# ProPrj_keyboard_2024-11-03.net
KiCad netlist of a schematic drawn in EasyEDA Pro
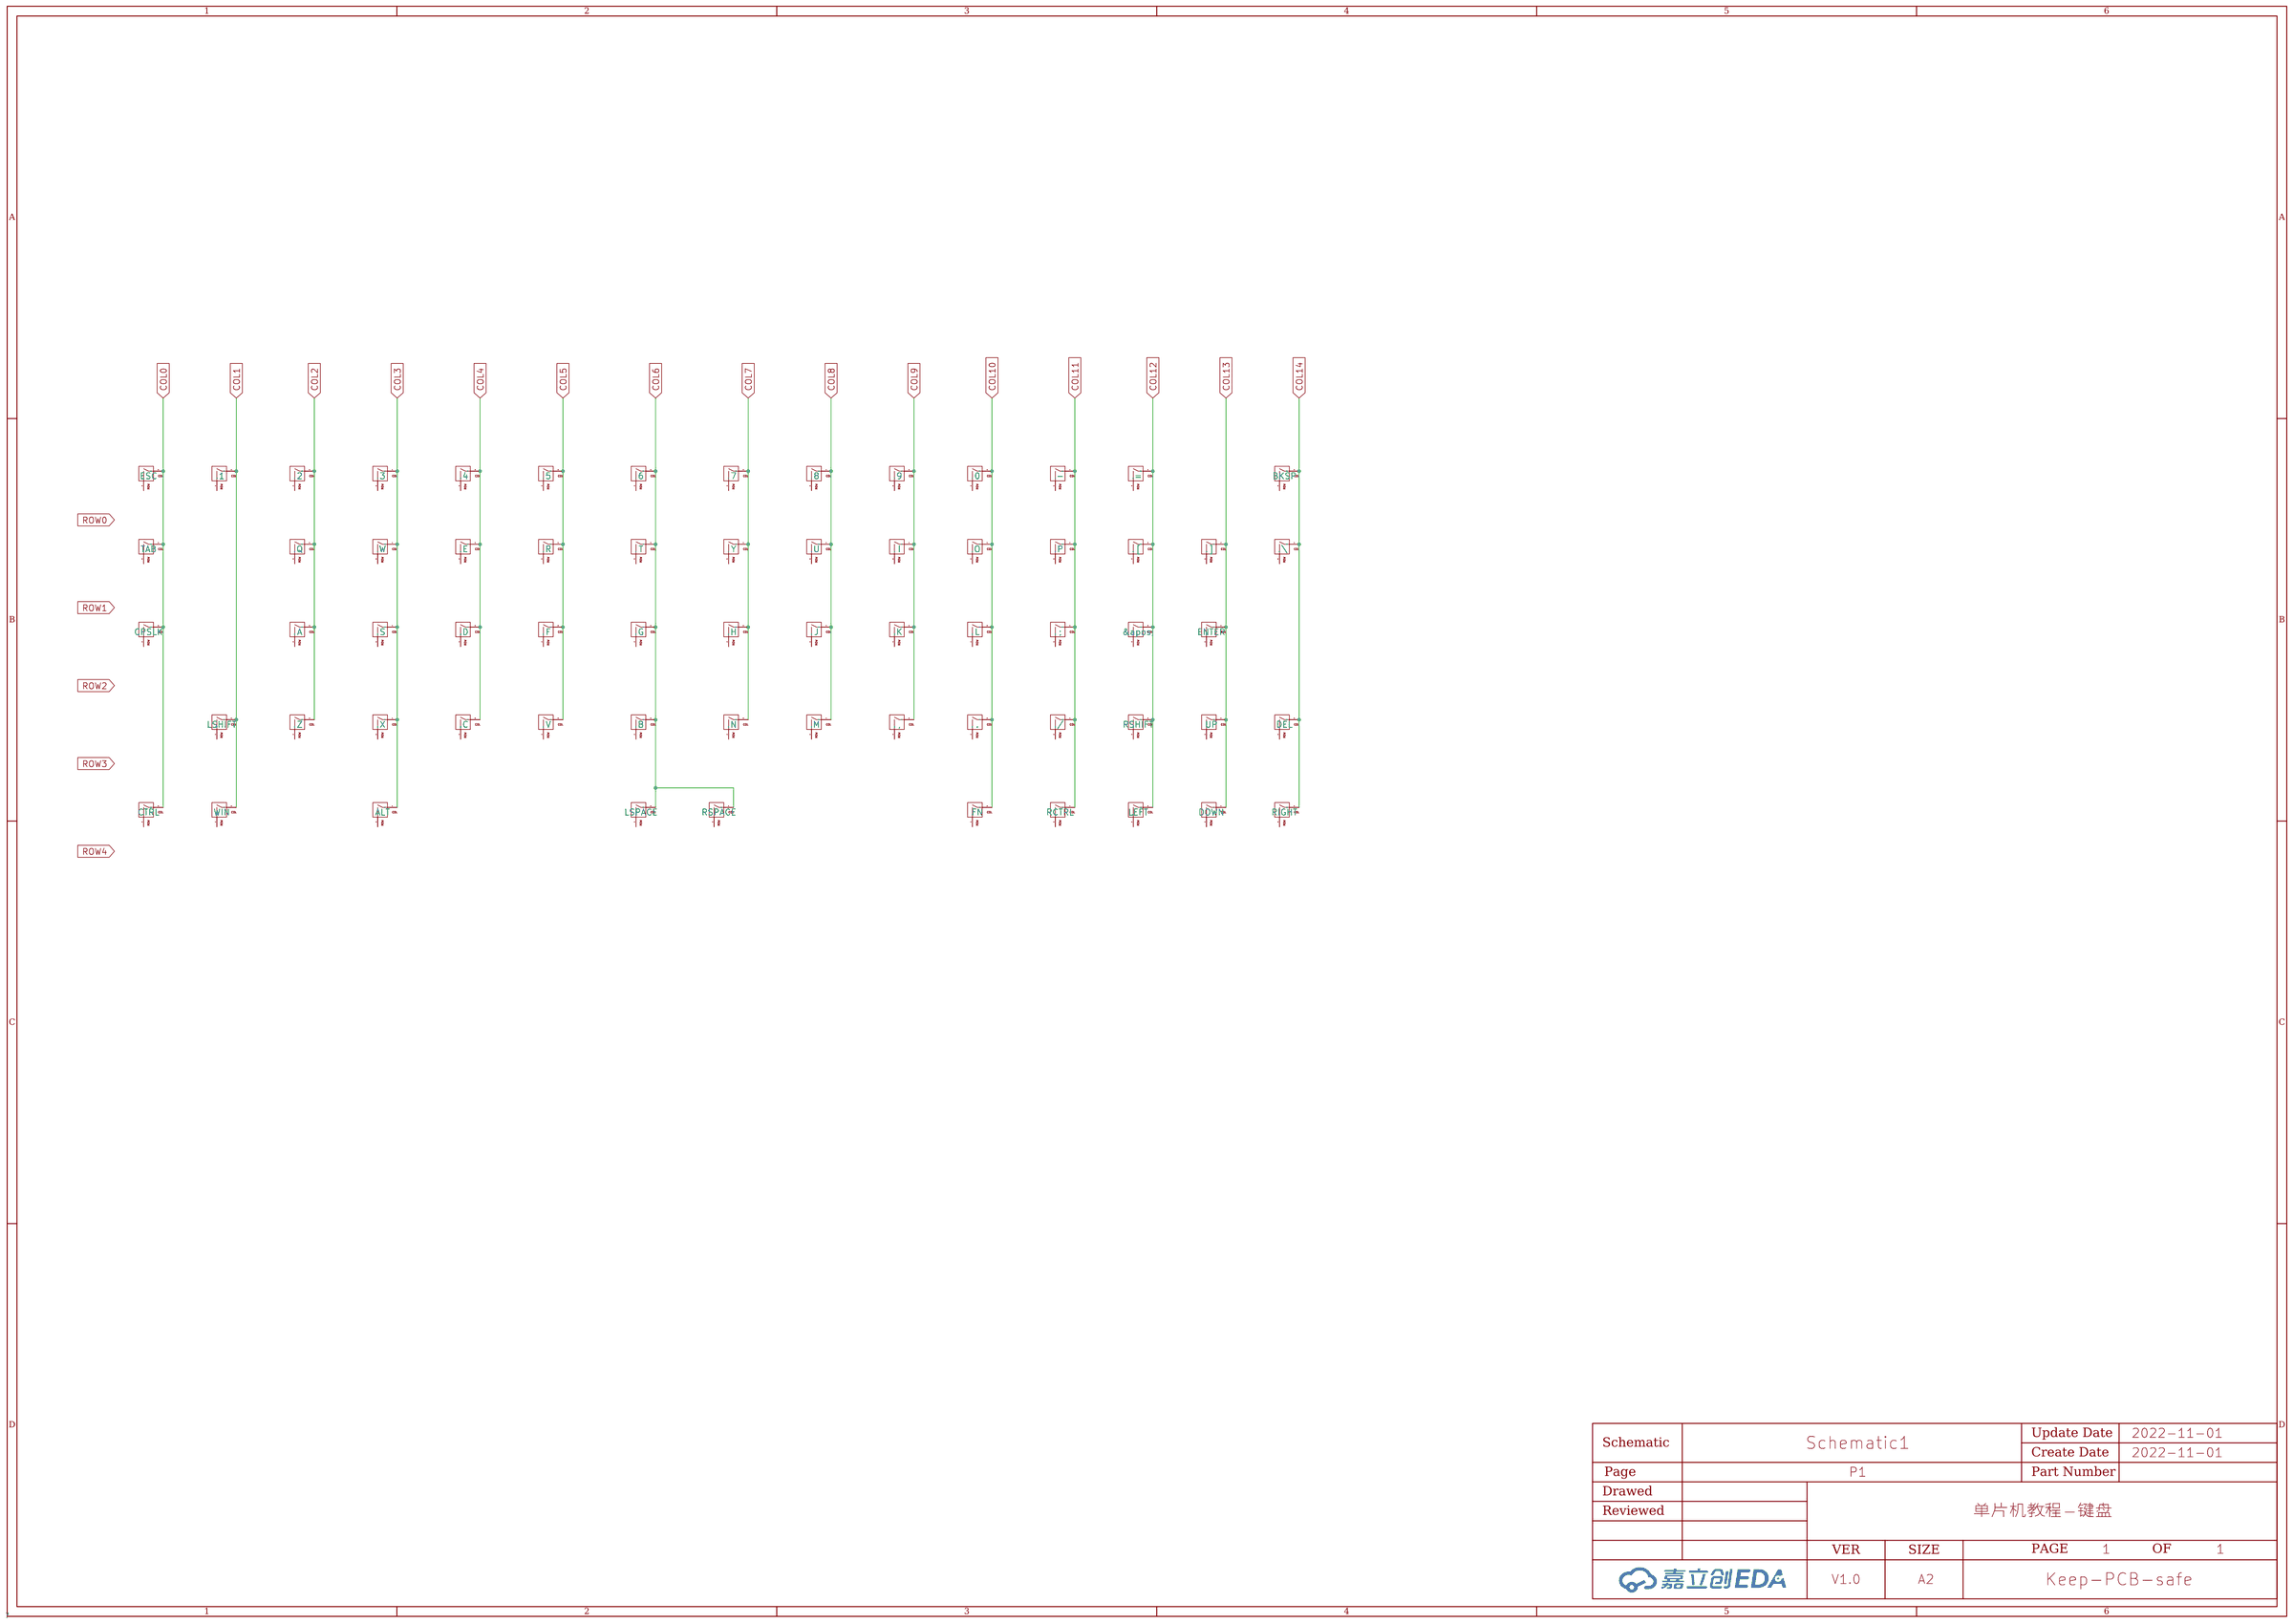
[diagram p0: schematic sheet]

(export (version "E")
  (design (tool "Eeschema 10.0.6"))
  (components
    (comp (ref "&apos;")
      (value "MX-NoLED")
      (footprint "easyedapro:MX_ALPS_HYBRID:MXONLY-1U")
      (libsource (lib "easyedapro") (part "MX-NoLED"))
    )
    (comp (ref ",")
      (value "MX-NoLED")
      (footprint "easyedapro:MX_ALPS_HYBRID:MXONLY-1U")
      (libsource (lib "easyedapro") (part "MX-NoLED"))
    )
    (comp (ref "-")
      (value "MX-NoLED")
      (footprint "easyedapro:MX_ALPS_HYBRID:MXONLY-1U")
      (libsource (lib "easyedapro") (part "MX-NoLED"))
    )
    (comp (ref ".")
      (value "MX-NoLED")
      (footprint "easyedapro:MX_ALPS_HYBRID:MXONLY-1U")
      (libsource (lib "easyedapro") (part "MX-NoLED"))
    )
    (comp (ref "/")
      (value "MX-NoLED")
      (footprint "easyedapro:MX_ALPS_HYBRID:MXONLY-1U")
      (libsource (lib "easyedapro") (part "MX-NoLED"))
    )
    (comp (ref "0")
      (value "MX-NoLED")
      (footprint "easyedapro:MX_ALPS_HYBRID:MXONLY-1U")
      (libsource (lib "easyedapro") (part "MX-NoLED"))
    )
    (comp (ref "1")
      (value "MX-NoLED")
      (footprint "easyedapro:MX_ALPS_HYBRID:MXONLY-1U")
      (libsource (lib "easyedapro") (part "MX-NoLED"))
    )
    (comp (ref "2")
      (value "MX-NoLED")
      (footprint "easyedapro:MX_ALPS_HYBRID:MXONLY-1U")
      (libsource (lib "easyedapro") (part "MX-NoLED"))
    )
    (comp (ref "3")
      (value "MX-NoLED")
      (footprint "easyedapro:MX_ALPS_HYBRID:MXONLY-1U")
      (libsource (lib "easyedapro") (part "MX-NoLED"))
    )
    (comp (ref "4")
      (value "MX-NoLED")
      (footprint "easyedapro:MX_ALPS_HYBRID:MXONLY-1U")
      (libsource (lib "easyedapro") (part "MX-NoLED"))
    )
    (comp (ref "5")
      (value "MX-NoLED")
      (footprint "easyedapro:MX_ALPS_HYBRID:MXONLY-1U")
      (libsource (lib "easyedapro") (part "MX-NoLED"))
    )
    (comp (ref "6")
      (value "MX-NoLED")
      (footprint "easyedapro:MX_ALPS_HYBRID:MXONLY-1U")
      (libsource (lib "easyedapro") (part "MX-NoLED"))
    )
    (comp (ref "7")
      (value "MX-NoLED")
      (footprint "easyedapro:MX_ALPS_HYBRID:MXONLY-1U")
      (libsource (lib "easyedapro") (part "MX-NoLED"))
    )
    (comp (ref "8")
      (value "MX-NoLED")
      (footprint "easyedapro:MX_ALPS_HYBRID:MXONLY-1U")
      (libsource (lib "easyedapro") (part "MX-NoLED"))
    )
    (comp (ref "9")
      (value "MX-NoLED")
      (footprint "easyedapro:MX_ALPS_HYBRID:MXONLY-1U")
      (libsource (lib "easyedapro") (part "MX-NoLED"))
    )
    (comp (ref ";")
      (value "MX-NoLED")
      (footprint "easyedapro:MX_ALPS_HYBRID:MXONLY-1U")
      (libsource (lib "easyedapro") (part "MX-NoLED"))
    )
    (comp (ref "=")
      (value "MX-NoLED")
      (footprint "easyedapro:MX_ALPS_HYBRID:MXONLY-1U")
      (libsource (lib "easyedapro") (part "MX-NoLED"))
    )
    (comp (ref "A")
      (value "MX-NoLED")
      (footprint "easyedapro:MX_ALPS_HYBRID:MXONLY-1U")
      (libsource (lib "easyedapro") (part "MX-NoLED"))
    )
    (comp (ref "ALT")
      (value "MX-NoLED")
      (footprint "easyedapro:MX_ALPS_HYBRID:MXONLY-1U")
      (libsource (lib "easyedapro") (part "MX-NoLED"))
    )
    (comp (ref "B")
      (value "MX-NoLED")
      (footprint "easyedapro:MX_ALPS_HYBRID:MXONLY-1U")
      (libsource (lib "easyedapro") (part "MX-NoLED"))
    )
    (comp (ref "BKSP")
      (value "MX-NoLED")
      (footprint "easyedapro:MX_ALPS_HYBRID:MXONLY-1U")
      (libsource (lib "easyedapro") (part "MX-NoLED"))
    )
    (comp (ref "C")
      (value "MX-NoLED")
      (footprint "easyedapro:MX_ALPS_HYBRID:MXONLY-1U")
      (libsource (lib "easyedapro") (part "MX-NoLED"))
    )
    (comp (ref "CPSLK")
      (value "MX-NoLED")
      (footprint "easyedapro:MX_ALPS_HYBRID:MXONLY-1U")
      (libsource (lib "easyedapro") (part "MX-NoLED"))
    )
    (comp (ref "CTRL")
      (value "MX-NoLED")
      (footprint "easyedapro:MX_ALPS_HYBRID:MXONLY-1U")
      (libsource (lib "easyedapro") (part "MX-NoLED"))
    )
    (comp (ref "D")
      (value "MX-NoLED")
      (footprint "easyedapro:MX_ALPS_HYBRID:MXONLY-1U")
      (libsource (lib "easyedapro") (part "MX-NoLED"))
    )
    (comp (ref "DEL")
      (value "MX-NoLED")
      (footprint "easyedapro:MX_ALPS_HYBRID:MXONLY-1U")
      (libsource (lib "easyedapro") (part "MX-NoLED"))
    )
    (comp (ref "DOWN")
      (value "MX-NoLED")
      (footprint "easyedapro:MX_ALPS_HYBRID:MXONLY-1U")
      (libsource (lib "easyedapro") (part "MX-NoLED"))
    )
    (comp (ref "E")
      (value "MX-NoLED")
      (footprint "easyedapro:MX_ALPS_HYBRID:MXONLY-1U")
      (libsource (lib "easyedapro") (part "MX-NoLED"))
    )
    (comp (ref "ENTER")
      (value "MX-NoLED")
      (footprint "easyedapro:MX_ALPS_HYBRID:MXONLY-1U")
      (libsource (lib "easyedapro") (part "MX-NoLED"))
    )
    (comp (ref "ESC")
      (value "MX-NoLED")
      (footprint "easyedapro:MX_ALPS_HYBRID:MXONLY-1U")
      (libsource (lib "easyedapro") (part "MX-NoLED"))
    )
    (comp (ref "F")
      (value "MX-NoLED")
      (footprint "easyedapro:MX_ALPS_HYBRID:MXONLY-1U")
      (libsource (lib "easyedapro") (part "MX-NoLED"))
    )
    (comp (ref "FN")
      (value "MX-NoLED")
      (footprint "easyedapro:MX_ALPS_HYBRID:MXONLY-1U")
      (libsource (lib "easyedapro") (part "MX-NoLED"))
    )
    (comp (ref "G")
      (value "MX-NoLED")
      (footprint "easyedapro:MX_ALPS_HYBRID:MXONLY-1U")
      (libsource (lib "easyedapro") (part "MX-NoLED"))
    )
    (comp (ref "H")
      (value "MX-NoLED")
      (footprint "easyedapro:MX_ALPS_HYBRID:MXONLY-1U")
      (libsource (lib "easyedapro") (part "MX-NoLED"))
    )
    (comp (ref "I")
      (value "MX-NoLED")
      (footprint "easyedapro:MX_ALPS_HYBRID:MXONLY-1U")
      (libsource (lib "easyedapro") (part "MX-NoLED"))
    )
    (comp (ref "J")
      (value "MX-NoLED")
      (footprint "easyedapro:MX_ALPS_HYBRID:MXONLY-1U")
      (libsource (lib "easyedapro") (part "MX-NoLED"))
    )
    (comp (ref "K")
      (value "MX-NoLED")
      (footprint "easyedapro:MX_ALPS_HYBRID:MXONLY-1U")
      (libsource (lib "easyedapro") (part "MX-NoLED"))
    )
    (comp (ref "L")
      (value "MX-NoLED")
      (footprint "easyedapro:MX_ALPS_HYBRID:MXONLY-1U")
      (libsource (lib "easyedapro") (part "MX-NoLED"))
    )
    (comp (ref "LEFT")
      (value "MX-NoLED")
      (footprint "easyedapro:MX_ALPS_HYBRID:MXONLY-1U")
      (libsource (lib "easyedapro") (part "MX-NoLED"))
    )
    (comp (ref "LSHIFT")
      (value "MX-NoLED")
      (footprint "easyedapro:MX_ALPS_HYBRID:MXONLY-1U")
      (libsource (lib "easyedapro") (part "MX-NoLED"))
    )
    (comp (ref "LSPACE")
      (value "MX-NoLED")
      (footprint "easyedapro:MX_ALPS_HYBRID:MXONLY-1U")
      (libsource (lib "easyedapro") (part "MX-NoLED"))
    )
    (comp (ref "M")
      (value "MX-NoLED")
      (footprint "easyedapro:MX_ALPS_HYBRID:MXONLY-1U")
      (libsource (lib "easyedapro") (part "MX-NoLED"))
    )
    (comp (ref "N")
      (value "MX-NoLED")
      (footprint "easyedapro:MX_ALPS_HYBRID:MXONLY-1U")
      (libsource (lib "easyedapro") (part "MX-NoLED"))
    )
    (comp (ref "O")
      (value "MX-NoLED")
      (footprint "easyedapro:MX_ALPS_HYBRID:MXONLY-1U")
      (libsource (lib "easyedapro") (part "MX-NoLED"))
    )
    (comp (ref "P")
      (value "MX-NoLED")
      (footprint "easyedapro:MX_ALPS_HYBRID:MXONLY-1U")
      (libsource (lib "easyedapro") (part "MX-NoLED"))
    )
    (comp (ref "Q")
      (value "MX-NoLED")
      (footprint "easyedapro:MX_ALPS_HYBRID:MXONLY-1U")
      (libsource (lib "easyedapro") (part "MX-NoLED"))
    )
    (comp (ref "R")
      (value "MX-NoLED")
      (footprint "easyedapro:MX_ALPS_HYBRID:MXONLY-1U")
      (libsource (lib "easyedapro") (part "MX-NoLED"))
    )
    (comp (ref "RCTRL")
      (value "MX-NoLED")
      (footprint "easyedapro:MX_ALPS_HYBRID:MXONLY-1U")
      (libsource (lib "easyedapro") (part "MX-NoLED"))
    )
    (comp (ref "RIGHT")
      (value "MX-NoLED")
      (footprint "easyedapro:MX_ALPS_HYBRID:MXONLY-1U")
      (libsource (lib "easyedapro") (part "MX-NoLED"))
    )
    (comp (ref "RSHIFT")
      (value "MX-NoLED")
      (footprint "easyedapro:MX_ALPS_HYBRID:MXONLY-1U")
      (libsource (lib "easyedapro") (part "MX-NoLED"))
    )
    (comp (ref "RSPACE")
      (value "MX-NoLED")
      (footprint "easyedapro:MX_ALPS_HYBRID:MXONLY-1U")
      (libsource (lib "easyedapro") (part "MX-NoLED"))
    )
    (comp (ref "S")
      (value "MX-NoLED")
      (footprint "easyedapro:MX_ALPS_HYBRID:MXONLY-1U")
      (libsource (lib "easyedapro") (part "MX-NoLED"))
    )
    (comp (ref "T")
      (value "MX-NoLED")
      (footprint "easyedapro:MX_ALPS_HYBRID:MXONLY-1U")
      (libsource (lib "easyedapro") (part "MX-NoLED"))
    )
    (comp (ref "TAB")
      (value "MX-NoLED")
      (footprint "easyedapro:MX_ALPS_HYBRID:MXONLY-1U")
      (libsource (lib "easyedapro") (part "MX-NoLED"))
    )
    (comp (ref "U")
      (value "MX-NoLED")
      (footprint "easyedapro:MX_ALPS_HYBRID:MXONLY-1U")
      (libsource (lib "easyedapro") (part "MX-NoLED"))
    )
    (comp (ref "UP")
      (value "MX-NoLED")
      (footprint "easyedapro:MX_ALPS_HYBRID:MXONLY-1U")
      (libsource (lib "easyedapro") (part "MX-NoLED"))
    )
    (comp (ref "V")
      (value "MX-NoLED")
      (footprint "easyedapro:MX_ALPS_HYBRID:MXONLY-1U")
      (libsource (lib "easyedapro") (part "MX-NoLED"))
    )
    (comp (ref "W")
      (value "MX-NoLED")
      (footprint "easyedapro:MX_ALPS_HYBRID:MXONLY-1U")
      (libsource (lib "easyedapro") (part "MX-NoLED"))
    )
    (comp (ref "WIN")
      (value "MX-NoLED")
      (footprint "easyedapro:MX_ALPS_HYBRID:MXONLY-1U")
      (libsource (lib "easyedapro") (part "MX-NoLED"))
    )
    (comp (ref "X")
      (value "MX-NoLED")
      (footprint "easyedapro:MX_ALPS_HYBRID:MXONLY-1U")
      (libsource (lib "easyedapro") (part "MX-NoLED"))
    )
    (comp (ref "Y")
      (value "MX-NoLED")
      (footprint "easyedapro:MX_ALPS_HYBRID:MXONLY-1U")
      (libsource (lib "easyedapro") (part "MX-NoLED"))
    )
    (comp (ref "Z")
      (value "MX-NoLED")
      (footprint "easyedapro:MX_ALPS_HYBRID:MXONLY-1U")
      (libsource (lib "easyedapro") (part "MX-NoLED"))
    )
    (comp (ref "[")
      (value "MX-NoLED")
      (footprint "easyedapro:MX_ALPS_HYBRID:MXONLY-1U")
      (libsource (lib "easyedapro") (part "MX-NoLED"))
    )
    (comp (ref "\\")
      (value "MX-NoLED")
      (footprint "easyedapro:MX_ALPS_HYBRID:MXONLY-1U")
      (libsource (lib "easyedapro") (part "MX-NoLED"))
    )
    (comp (ref "]")
      (value "MX-NoLED")
      (footprint "easyedapro:MX_ALPS_HYBRID:MXONLY-1U")
      (libsource (lib "easyedapro") (part "MX-NoLED"))
    )
  )
  (nets
    (net (code "1") (name "COL0") (class "Default")
      (node (ref "CPSLK") (pin "1") (pinfunction "COL_1") (pintype "unspecified"))
      (node (ref "CTRL") (pin "1") (pinfunction "COL_1") (pintype "unspecified"))
      (node (ref "ESC") (pin "1") (pinfunction "COL_1") (pintype "unspecified"))
      (node (ref "TAB") (pin "1") (pinfunction "COL_1") (pintype "unspecified"))
    )
    (net (code "2") (name "COL1") (class "Default")
      (node (ref "1") (pin "1") (pinfunction "COL_1") (pintype "unspecified"))
      (node (ref "LSHIFT") (pin "1") (pinfunction "COL_1") (pintype "unspecified"))
      (node (ref "WIN") (pin "1") (pinfunction "COL_1") (pintype "unspecified"))
    )
    (net (code "3") (name "COL2") (class "Default")
      (node (ref "2") (pin "1") (pinfunction "COL_1") (pintype "unspecified"))
      (node (ref "A") (pin "1") (pinfunction "COL_1") (pintype "unspecified"))
      (node (ref "Q") (pin "1") (pinfunction "COL_1") (pintype "unspecified"))
      (node (ref "Z") (pin "1") (pinfunction "COL_1") (pintype "unspecified"))
    )
    (net (code "4") (name "COL3") (class "Default")
      (node (ref "3") (pin "1") (pinfunction "COL_1") (pintype "unspecified"))
      (node (ref "ALT") (pin "1") (pinfunction "COL_1") (pintype "unspecified"))
      (node (ref "S") (pin "1") (pinfunction "COL_1") (pintype "unspecified"))
      (node (ref "W") (pin "1") (pinfunction "COL_1") (pintype "unspecified"))
      (node (ref "X") (pin "1") (pinfunction "COL_1") (pintype "unspecified"))
    )
    (net (code "5") (name "COL4") (class "Default")
      (node (ref "4") (pin "1") (pinfunction "COL_1") (pintype "unspecified"))
      (node (ref "C") (pin "1") (pinfunction "COL_1") (pintype "unspecified"))
      (node (ref "D") (pin "1") (pinfunction "COL_1") (pintype "unspecified"))
      (node (ref "E") (pin "1") (pinfunction "COL_1") (pintype "unspecified"))
    )
    (net (code "6") (name "COL5") (class "Default")
      (node (ref "5") (pin "1") (pinfunction "COL_1") (pintype "unspecified"))
      (node (ref "F") (pin "1") (pinfunction "COL_1") (pintype "unspecified"))
      (node (ref "R") (pin "1") (pinfunction "COL_1") (pintype "unspecified"))
      (node (ref "V") (pin "1") (pinfunction "COL_1") (pintype "unspecified"))
    )
    (net (code "7") (name "COL6") (class "Default")
      (node (ref "6") (pin "1") (pinfunction "COL_1") (pintype "unspecified"))
      (node (ref "B") (pin "1") (pinfunction "COL_1") (pintype "unspecified"))
      (node (ref "G") (pin "1") (pinfunction "COL_1") (pintype "unspecified"))
      (node (ref "LSPACE") (pin "1") (pinfunction "COL_1") (pintype "unspecified"))
      (node (ref "RSPACE") (pin "1") (pinfunction "COL_1") (pintype "unspecified"))
      (node (ref "T") (pin "1") (pinfunction "COL_1") (pintype "unspecified"))
    )
    (net (code "8") (name "COL7") (class "Default")
      (node (ref "7") (pin "1") (pinfunction "COL_1") (pintype "unspecified"))
      (node (ref "H") (pin "1") (pinfunction "COL_1") (pintype "unspecified"))
      (node (ref "N") (pin "1") (pinfunction "COL_1") (pintype "unspecified"))
      (node (ref "Y") (pin "1") (pinfunction "COL_1") (pintype "unspecified"))
    )
    (net (code "9") (name "COL8") (class "Default")
      (node (ref "8") (pin "1") (pinfunction "COL_1") (pintype "unspecified"))
      (node (ref "J") (pin "1") (pinfunction "COL_1") (pintype "unspecified"))
      (node (ref "M") (pin "1") (pinfunction "COL_1") (pintype "unspecified"))
      (node (ref "U") (pin "1") (pinfunction "COL_1") (pintype "unspecified"))
    )
    (net (code "10") (name "COL9") (class "Default")
      (node (ref ",") (pin "1") (pinfunction "COL_1") (pintype "unspecified"))
      (node (ref "9") (pin "1") (pinfunction "COL_1") (pintype "unspecified"))
      (node (ref "I") (pin "1") (pinfunction "COL_1") (pintype "unspecified"))
      (node (ref "K") (pin "1") (pinfunction "COL_1") (pintype "unspecified"))
    )
    (net (code "11") (name "COL10") (class "Default")
      (node (ref ".") (pin "1") (pinfunction "COL_1") (pintype "unspecified"))
      (node (ref "0") (pin "1") (pinfunction "COL_1") (pintype "unspecified"))
      (node (ref "FN") (pin "1") (pinfunction "COL_1") (pintype "unspecified"))
      (node (ref "L") (pin "1") (pinfunction "COL_1") (pintype "unspecified"))
      (node (ref "O") (pin "1") (pinfunction "COL_1") (pintype "unspecified"))
    )
    (net (code "12") (name "COL11") (class "Default")
      (node (ref "-") (pin "1") (pinfunction "COL_1") (pintype "unspecified"))
      (node (ref "/") (pin "1") (pinfunction "COL_1") (pintype "unspecified"))
      (node (ref ";") (pin "1") (pinfunction "COL_1") (pintype "unspecified"))
      (node (ref "P") (pin "1") (pinfunction "COL_1") (pintype "unspecified"))
      (node (ref "RCTRL") (pin "1") (pinfunction "COL_1") (pintype "unspecified"))
    )
    (net (code "13") (name "COL12") (class "Default")
      (node (ref "&apos;") (pin "1") (pinfunction "COL_1") (pintype "unspecified"))
      (node (ref "=") (pin "1") (pinfunction "COL_1") (pintype "unspecified"))
      (node (ref "LEFT") (pin "1") (pinfunction "COL_1") (pintype "unspecified"))
      (node (ref "RSHIFT") (pin "1") (pinfunction "COL_1") (pintype "unspecified"))
      (node (ref "[") (pin "1") (pinfunction "COL_1") (pintype "unspecified"))
    )
    (net (code "14") (name "COL13") (class "Default")
      (node (ref "DOWN") (pin "1") (pinfunction "COL_1") (pintype "unspecified"))
      (node (ref "ENTER") (pin "1") (pinfunction "COL_1") (pintype "unspecified"))
      (node (ref "UP") (pin "1") (pinfunction "COL_1") (pintype "unspecified"))
      (node (ref "]") (pin "1") (pinfunction "COL_1") (pintype "unspecified"))
    )
    (net (code "15") (name "COL14") (class "Default")
      (node (ref "BKSP") (pin "1") (pinfunction "COL_1") (pintype "unspecified"))
      (node (ref "DEL") (pin "1") (pinfunction "COL_1") (pintype "unspecified"))
      (node (ref "RIGHT") (pin "1") (pinfunction "COL_1") (pintype "unspecified"))
      (node (ref "\\") (pin "1") (pinfunction "COL_1") (pintype "unspecified"))
    )
    (net (code "21") (name "unconnected-(&apos;-ROW-Pad2)") (class "Default")
      (node (ref "&apos;") (pin "2") (pinfunction "ROW_2") (pintype "unspecified"))
    )
    (net (code "22") (name "unconnected-(,-ROW-Pad2)") (class "Default")
      (node (ref ",") (pin "2") (pinfunction "ROW_2") (pintype "unspecified"))
    )
    (net (code "23") (name "unconnected-(--ROW-Pad2)") (class "Default")
      (node (ref "-") (pin "2") (pinfunction "ROW_2") (pintype "unspecified"))
    )
    (net (code "24") (name "unconnected-(.-ROW-Pad2)") (class "Default")
      (node (ref ".") (pin "2") (pinfunction "ROW_2") (pintype "unspecified"))
    )
    (net (code "25") (name "unconnected-(/-ROW-Pad2)") (class "Default")
      (node (ref "/") (pin "2") (pinfunction "ROW_2") (pintype "unspecified"))
    )
    (net (code "26") (name "unconnected-(0-ROW-Pad2)") (class "Default")
      (node (ref "0") (pin "2") (pinfunction "ROW_2") (pintype "unspecified"))
    )
    (net (code "27") (name "unconnected-(1-ROW-Pad2)") (class "Default")
      (node (ref "1") (pin "2") (pinfunction "ROW_2") (pintype "unspecified"))
    )
    (net (code "28") (name "unconnected-(2-ROW-Pad2)") (class "Default")
      (node (ref "2") (pin "2") (pinfunction "ROW_2") (pintype "unspecified"))
    )
    (net (code "29") (name "unconnected-(3-ROW-Pad2)") (class "Default")
      (node (ref "3") (pin "2") (pinfunction "ROW_2") (pintype "unspecified"))
    )
    (net (code "30") (name "unconnected-(4-ROW-Pad2)") (class "Default")
      (node (ref "4") (pin "2") (pinfunction "ROW_2") (pintype "unspecified"))
    )
    (net (code "31") (name "unconnected-(5-ROW-Pad2)") (class "Default")
      (node (ref "5") (pin "2") (pinfunction "ROW_2") (pintype "unspecified"))
    )
    (net (code "32") (name "unconnected-(6-ROW-Pad2)") (class "Default")
      (node (ref "6") (pin "2") (pinfunction "ROW_2") (pintype "unspecified"))
    )
    (net (code "33") (name "unconnected-(7-ROW-Pad2)") (class "Default")
      (node (ref "7") (pin "2") (pinfunction "ROW_2") (pintype "unspecified"))
    )
    (net (code "34") (name "unconnected-(8-ROW-Pad2)") (class "Default")
      (node (ref "8") (pin "2") (pinfunction "ROW_2") (pintype "unspecified"))
    )
    (net (code "35") (name "unconnected-(9-ROW-Pad2)") (class "Default")
      (node (ref "9") (pin "2") (pinfunction "ROW_2") (pintype "unspecified"))
    )
    (net (code "36") (name "unconnected-(;-ROW-Pad2)") (class "Default")
      (node (ref ";") (pin "2") (pinfunction "ROW_2") (pintype "unspecified"))
    )
    (net (code "37") (name "unconnected-(=-ROW-Pad2)") (class "Default")
      (node (ref "=") (pin "2") (pinfunction "ROW_2") (pintype "unspecified"))
    )
    (net (code "38") (name "unconnected-(A-ROW-Pad2)") (class "Default")
      (node (ref "A") (pin "2") (pinfunction "ROW_2") (pintype "unspecified"))
    )
    (net (code "39") (name "unconnected-(ALT-ROW-Pad2)") (class "Default")
      (node (ref "ALT") (pin "2") (pinfunction "ROW_2") (pintype "unspecified"))
    )
    (net (code "40") (name "unconnected-(B-ROW-Pad2)") (class "Default")
      (node (ref "B") (pin "2") (pinfunction "ROW_2") (pintype "unspecified"))
    )
    (net (code "41") (name "unconnected-(BKSP-ROW-Pad2)") (class "Default")
      (node (ref "BKSP") (pin "2") (pinfunction "ROW_2") (pintype "unspecified"))
    )
    (net (code "42") (name "unconnected-(C-ROW-Pad2)") (class "Default")
      (node (ref "C") (pin "2") (pinfunction "ROW_2") (pintype "unspecified"))
    )
    (net (code "43") (name "unconnected-(CPSLK-ROW-Pad2)") (class "Default")
      (node (ref "CPSLK") (pin "2") (pinfunction "ROW_2") (pintype "unspecified"))
    )
    (net (code "44") (name "unconnected-(CTRL-ROW-Pad2)") (class "Default")
      (node (ref "CTRL") (pin "2") (pinfunction "ROW_2") (pintype "unspecified"))
    )
    (net (code "45") (name "unconnected-(D-ROW-Pad2)") (class "Default")
      (node (ref "D") (pin "2") (pinfunction "ROW_2") (pintype "unspecified"))
    )
    (net (code "46") (name "unconnected-(DEL-ROW-Pad2)") (class "Default")
      (node (ref "DEL") (pin "2") (pinfunction "ROW_2") (pintype "unspecified"))
    )
    (net (code "47") (name "unconnected-(DOWN-ROW-Pad2)") (class "Default")
      (node (ref "DOWN") (pin "2") (pinfunction "ROW_2") (pintype "unspecified"))
    )
    (net (code "48") (name "unconnected-(E-ROW-Pad2)") (class "Default")
      (node (ref "E") (pin "2") (pinfunction "ROW_2") (pintype "unspecified"))
    )
    (net (code "49") (name "unconnected-(ENTER-ROW-Pad2)") (class "Default")
      (node (ref "ENTER") (pin "2") (pinfunction "ROW_2") (pintype "unspecified"))
    )
    (net (code "50") (name "unconnected-(ESC-ROW-Pad2)") (class "Default")
      (node (ref "ESC") (pin "2") (pinfunction "ROW_2") (pintype "unspecified"))
    )
    (net (code "51") (name "unconnected-(F-ROW-Pad2)") (class "Default")
      (node (ref "F") (pin "2") (pinfunction "ROW_2") (pintype "unspecified"))
    )
    (net (code "52") (name "unconnected-(FN-ROW-Pad2)") (class "Default")
      (node (ref "FN") (pin "2") (pinfunction "ROW_2") (pintype "unspecified"))
    )
    (net (code "53") (name "unconnected-(G-ROW-Pad2)") (class "Default")
      (node (ref "G") (pin "2") (pinfunction "ROW_2") (pintype "unspecified"))
    )
    (net (code "54") (name "unconnected-(H-ROW-Pad2)") (class "Default")
      (node (ref "H") (pin "2") (pinfunction "ROW_2") (pintype "unspecified"))
    )
    (net (code "55") (name "unconnected-(I-ROW-Pad2)") (class "Default")
      (node (ref "I") (pin "2") (pinfunction "ROW_2") (pintype "unspecified"))
    )
    (net (code "56") (name "unconnected-(J-ROW-Pad2)") (class "Default")
      (node (ref "J") (pin "2") (pinfunction "ROW_2") (pintype "unspecified"))
    )
    (net (code "57") (name "unconnected-(K-ROW-Pad2)") (class "Default")
      (node (ref "K") (pin "2") (pinfunction "ROW_2") (pintype "unspecified"))
    )
    (net (code "58") (name "unconnected-(L-ROW-Pad2)") (class "Default")
      (node (ref "L") (pin "2") (pinfunction "ROW_2") (pintype "unspecified"))
    )
    (net (code "59") (name "unconnected-(LEFT-ROW-Pad2)") (class "Default")
      (node (ref "LEFT") (pin "2") (pinfunction "ROW_2") (pintype "unspecified"))
    )
    (net (code "60") (name "unconnected-(LSHIFT-ROW-Pad2)") (class "Default")
      (node (ref "LSHIFT") (pin "2") (pinfunction "ROW_2") (pintype "unspecified"))
    )
    (net (code "61") (name "unconnected-(LSPACE-ROW-Pad2)") (class "Default")
      (node (ref "LSPACE") (pin "2") (pinfunction "ROW_2") (pintype "unspecified"))
    )
    (net (code "62") (name "unconnected-(M-ROW-Pad2)") (class "Default")
      (node (ref "M") (pin "2") (pinfunction "ROW_2") (pintype "unspecified"))
    )
    (net (code "63") (name "unconnected-(N-ROW-Pad2)") (class "Default")
      (node (ref "N") (pin "2") (pinfunction "ROW_2") (pintype "unspecified"))
    )
    (net (code "64") (name "unconnected-(O-ROW-Pad2)") (class "Default")
      (node (ref "O") (pin "2") (pinfunction "ROW_2") (pintype "unspecified"))
    )
    (net (code "65") (name "unconnected-(P-ROW-Pad2)") (class "Default")
      (node (ref "P") (pin "2") (pinfunction "ROW_2") (pintype "unspecified"))
    )
    (net (code "66") (name "unconnected-(Q-ROW-Pad2)") (class "Default")
      (node (ref "Q") (pin "2") (pinfunction "ROW_2") (pintype "unspecified"))
    )
    (net (code "67") (name "unconnected-(R-ROW-Pad2)") (class "Default")
      (node (ref "R") (pin "2") (pinfunction "ROW_2") (pintype "unspecified"))
    )
    (net (code "68") (name "unconnected-(RCTRL-ROW-Pad2)") (class "Default")
      (node (ref "RCTRL") (pin "2") (pinfunction "ROW_2") (pintype "unspecified"))
    )
    (net (code "69") (name "unconnected-(RIGHT-ROW-Pad2)") (class "Default")
      (node (ref "RIGHT") (pin "2") (pinfunction "ROW_2") (pintype "unspecified"))
    )
    (net (code "70") (name "unconnected-(RSHIFT-ROW-Pad2)") (class "Default")
      (node (ref "RSHIFT") (pin "2") (pinfunction "ROW_2") (pintype "unspecified"))
    )
    (net (code "71") (name "unconnected-(RSPACE-ROW-Pad2)") (class "Default")
      (node (ref "RSPACE") (pin "2") (pinfunction "ROW_2") (pintype "unspecified"))
    )
    (net (code "72") (name "unconnected-(S-ROW-Pad2)") (class "Default")
      (node (ref "S") (pin "2") (pinfunction "ROW_2") (pintype "unspecified"))
    )
    (net (code "73") (name "unconnected-(T-ROW-Pad2)") (class "Default")
      (node (ref "T") (pin "2") (pinfunction "ROW_2") (pintype "unspecified"))
    )
    (net (code "74") (name "unconnected-(TAB-ROW-Pad2)") (class "Default")
      (node (ref "TAB") (pin "2") (pinfunction "ROW_2") (pintype "unspecified"))
    )
    (net (code "75") (name "unconnected-(U-ROW-Pad2)") (class "Default")
      (node (ref "U") (pin "2") (pinfunction "ROW_2") (pintype "unspecified"))
    )
    (net (code "76") (name "unconnected-(UP-ROW-Pad2)") (class "Default")
      (node (ref "UP") (pin "2") (pinfunction "ROW_2") (pintype "unspecified"))
    )
    (net (code "77") (name "unconnected-(V-ROW-Pad2)") (class "Default")
      (node (ref "V") (pin "2") (pinfunction "ROW_2") (pintype "unspecified"))
    )
    (net (code "78") (name "unconnected-(W-ROW-Pad2)") (class "Default")
      (node (ref "W") (pin "2") (pinfunction "ROW_2") (pintype "unspecified"))
    )
    (net (code "79") (name "unconnected-(WIN-ROW-Pad2)") (class "Default")
      (node (ref "WIN") (pin "2") (pinfunction "ROW_2") (pintype "unspecified"))
    )
    (net (code "80") (name "unconnected-(X-ROW-Pad2)") (class "Default")
      (node (ref "X") (pin "2") (pinfunction "ROW_2") (pintype "unspecified"))
    )
    (net (code "81") (name "unconnected-(Y-ROW-Pad2)") (class "Default")
      (node (ref "Y") (pin "2") (pinfunction "ROW_2") (pintype "unspecified"))
    )
    (net (code "82") (name "unconnected-(Z-ROW-Pad2)") (class "Default")
      (node (ref "Z") (pin "2") (pinfunction "ROW_2") (pintype "unspecified"))
    )
    (net (code "83") (name "unconnected-([-ROW-Pad2)") (class "Default")
      (node (ref "[") (pin "2") (pinfunction "ROW_2") (pintype "unspecified"))
    )
    (net (code "84") (name "unconnected-(\\-ROW-Pad2)") (class "Default")
      (node (ref "\\") (pin "2") (pinfunction "ROW_2") (pintype "unspecified"))
    )
    (net (code "85") (name "unconnected-(]-ROW-Pad2)") (class "Default")
      (node (ref "]") (pin "2") (pinfunction "ROW_2") (pintype "unspecified"))
    )
  )
)
